# Easy_LED.net
KiCad netlist of a schematic drawn in EAGLE
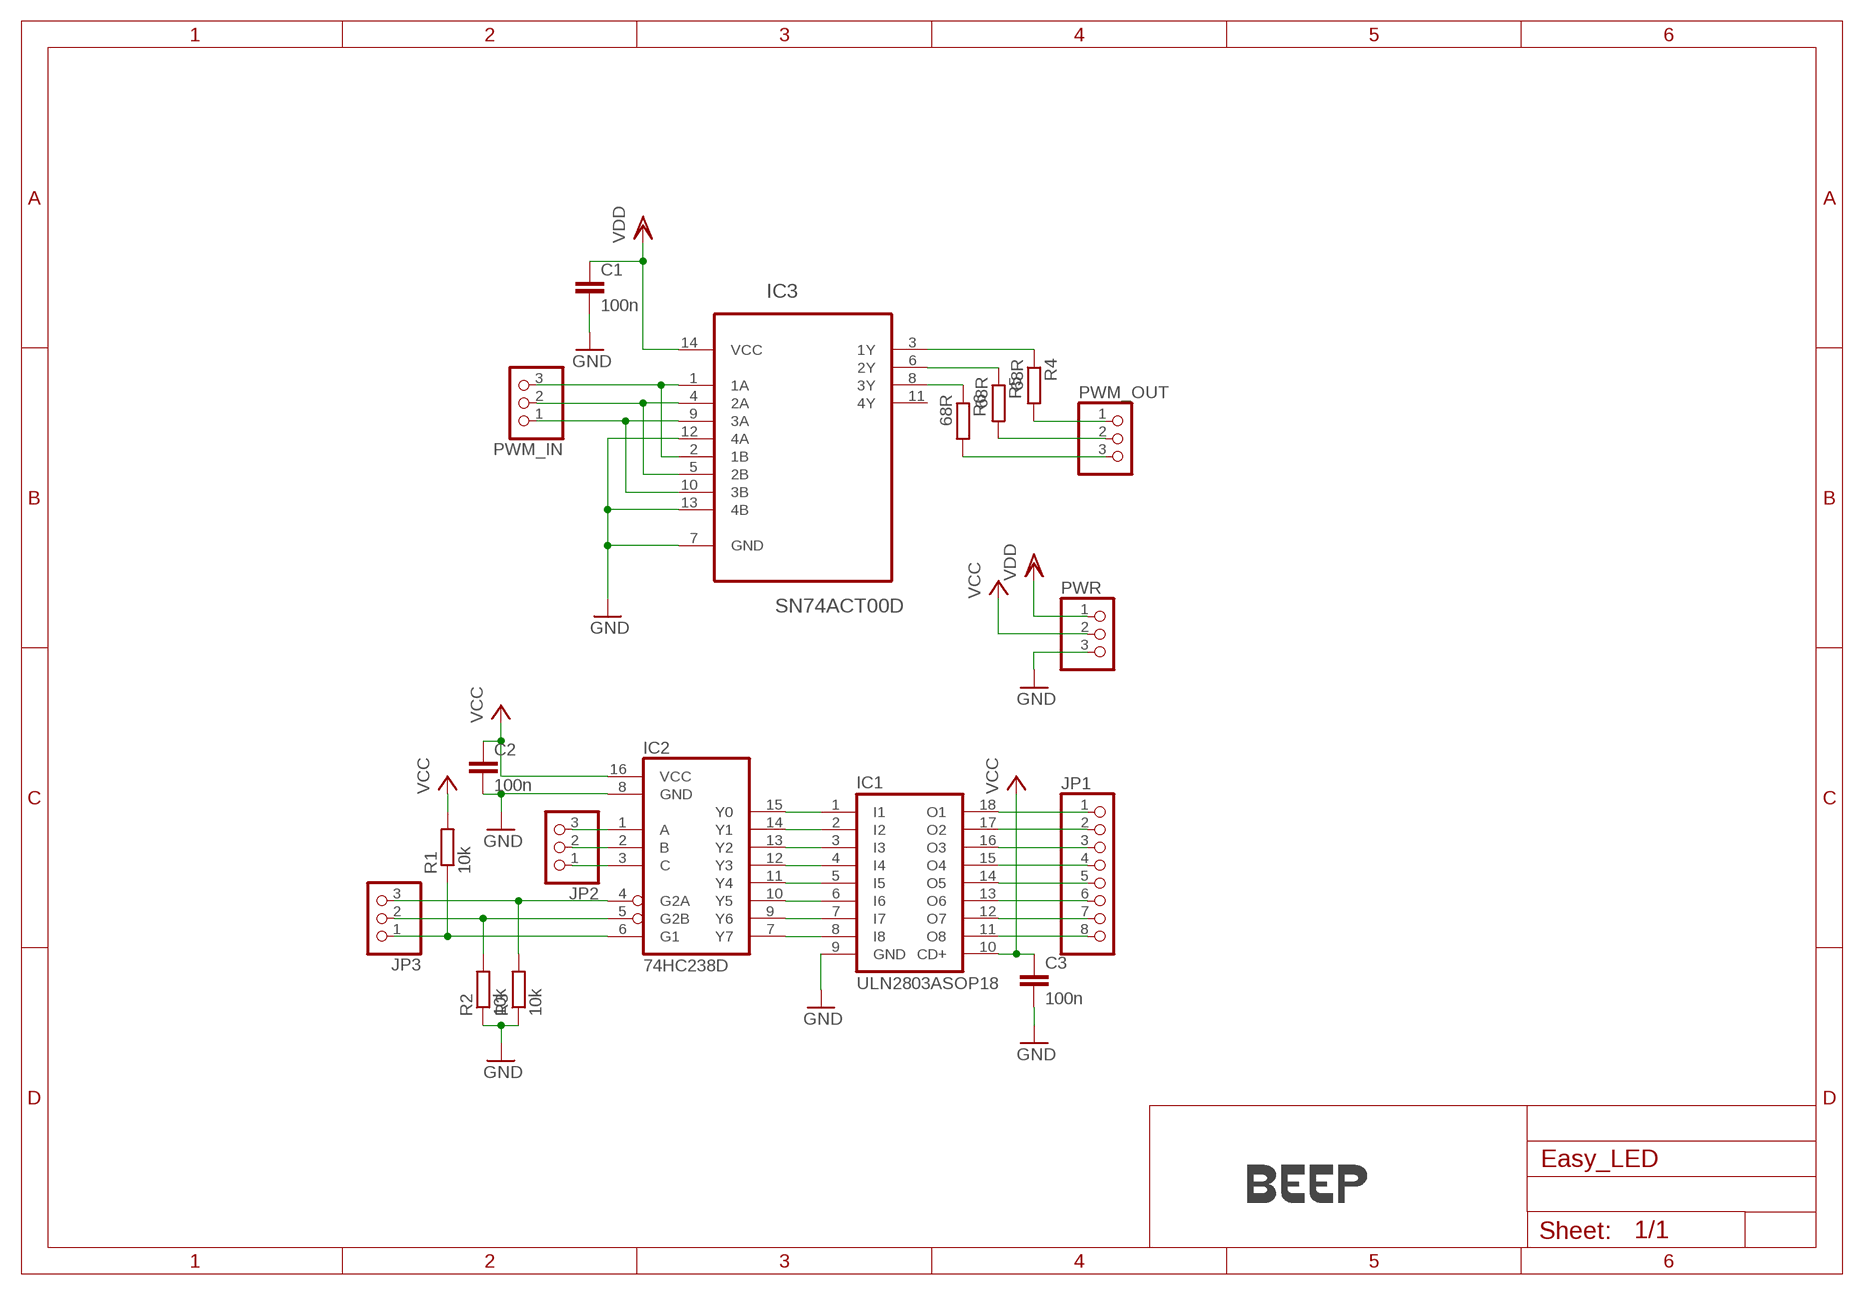
[diagram p0: schematic, sheet 1]

(export (version "E")
  (design (tool "Eeschema 10.0.6"))
  (components
    (comp (ref "C1")
      (value "100n")
      (footprint "eagle-import:C0805")
      (libsource (lib "eagle-import") (part "C-EUC0805"))
    )
    (comp (ref "C2")
      (value "100n")
      (footprint "eagle-import:C0805")
      (libsource (lib "eagle-import") (part "C-EUC0805"))
    )
    (comp (ref "C3")
      (value "100n")
      (footprint "eagle-import:C0805")
      (libsource (lib "eagle-import") (part "C-EUC0805"))
    )
    (comp (ref "IC1")
      (value "ULN2803ASOP18")
      (footprint "eagle-import:SOP18")
      (libsource (lib "eagle-import") (part "ULN2803ASOP18"))
    )
    (comp (ref "IC2")
      (value "74HC238D")
      (footprint "eagle-import:SO16")
      (libsource (lib "eagle-import") (part "74HC238D"))
    )
    (comp (ref "IC3")
      (value "SN74ACT00D")
      (footprint "eagle-import:SOIC127P600X175-14N")
      (libsource (lib "eagle-import") (part "SN74ACT00D"))
    )
    (comp (ref "JP1")
      (value "PINHD-1X8")
      (footprint "eagle-import:1X08")
      (libsource (lib "eagle-import") (part "PINHD-1X8"))
    )
    (comp (ref "JP2")
      (value "PINHD-1X3")
      (footprint "eagle-import:1X03")
      (libsource (lib "eagle-import") (part "PINHD-1X3"))
    )
    (comp (ref "JP3")
      (value "PINHD-1X3")
      (footprint "eagle-import:1X03")
      (libsource (lib "eagle-import") (part "PINHD-1X3"))
    )
    (comp (ref "PWM_IN")
      (value "PINHD-1X3")
      (footprint "eagle-import:1X03")
      (libsource (lib "eagle-import") (part "PINHD-1X3"))
    )
    (comp (ref "PWM_OUT")
      (value "PINHD-1X3")
      (footprint "eagle-import:1X03")
      (libsource (lib "eagle-import") (part "PINHD-1X3"))
    )
    (comp (ref "PWR")
      (value "PINHD-1X3")
      (footprint "eagle-import:1X03")
      (libsource (lib "eagle-import") (part "PINHD-1X3"))
    )
    (comp (ref "R1")
      (value "10k")
      (footprint "eagle-import:0207_7")
      (libsource (lib "eagle-import") (part "R-EU_0207/7"))
    )
    (comp (ref "R2")
      (value "10k")
      (footprint "eagle-import:M0805")
      (libsource (lib "eagle-import") (part "R-EU_M0805"))
    )
    (comp (ref "R3")
      (value "10k")
      (footprint "eagle-import:M0805")
      (libsource (lib "eagle-import") (part "R-EU_M0805"))
    )
    (comp (ref "R4")
      (value "68R")
      (footprint "eagle-import:M0805")
      (libsource (lib "eagle-import") (part "R-EU_M0805"))
    )
    (comp (ref "R5")
      (value "68R")
      (footprint "eagle-import:M0805")
      (libsource (lib "eagle-import") (part "R-EU_M0805"))
    )
    (comp (ref "R6")
      (value "68R")
      (footprint "eagle-import:M0805")
      (libsource (lib "eagle-import") (part "R-EU_M0805"))
    )
    (comp (ref "U$4")
      (value "LOGO-COPPER6")
      (footprint "eagle-import:COPPER6")
      (libsource (lib "eagle-import") (part "LOGO-COPPER6"))
    )
  )
  (nets
    (net (code "1") (name "GND") (class "Default")
      (node (ref "C1") (pin "2") (pinfunction "2_2") (pintype "passive"))
      (node (ref "C2") (pin "2") (pinfunction "2_2") (pintype "passive"))
      (node (ref "C3") (pin "2") (pinfunction "2_2") (pintype "passive"))
      (node (ref "IC1") (pin "9") (pinfunction "GND_9") (pintype "power_in"))
      (node (ref "IC2") (pin "8") (pinfunction "GND_8") (pintype "power_in"))
      (node (ref "IC3") (pin "12") (pinfunction "4A_12") (pintype "input"))
      (node (ref "IC3") (pin "13") (pinfunction "4B_13") (pintype "input"))
      (node (ref "IC3") (pin "7") (pinfunction "GND_7") (pintype "passive"))
      (node (ref "PWR") (pin "3") (pinfunction "3_3") (pintype "passive"))
      (node (ref "R2") (pin "1") (pinfunction "1_1") (pintype "passive"))
      (node (ref "R3") (pin "1") (pinfunction "1_1") (pintype "passive"))
    )
    (net (code "2") (name "Net-(IC1-I1)") (class "Default")
      (node (ref "IC1") (pin "1") (pinfunction "I1_1") (pintype "input"))
      (node (ref "IC2") (pin "15") (pinfunction "Y0_15") (pintype "output"))
    )
    (net (code "3") (name "Net-(IC1-I2)") (class "Default")
      (node (ref "IC1") (pin "2") (pinfunction "I2_2") (pintype "input"))
      (node (ref "IC2") (pin "14") (pinfunction "Y1_14") (pintype "output"))
    )
    (net (code "4") (name "Net-(IC1-I3)") (class "Default")
      (node (ref "IC1") (pin "3") (pinfunction "I3_3") (pintype "input"))
      (node (ref "IC2") (pin "13") (pinfunction "Y2_13") (pintype "output"))
    )
    (net (code "5") (name "Net-(IC1-I4)") (class "Default")
      (node (ref "IC1") (pin "4") (pinfunction "I4_4") (pintype "input"))
      (node (ref "IC2") (pin "12") (pinfunction "Y3_12") (pintype "output"))
    )
    (net (code "6") (name "Net-(IC1-I5)") (class "Default")
      (node (ref "IC1") (pin "5") (pinfunction "I5_5") (pintype "input"))
      (node (ref "IC2") (pin "11") (pinfunction "Y4_11") (pintype "output"))
    )
    (net (code "7") (name "Net-(IC1-I6)") (class "Default")
      (node (ref "IC1") (pin "6") (pinfunction "I6_6") (pintype "input"))
      (node (ref "IC2") (pin "10") (pinfunction "Y5_10") (pintype "output"))
    )
    (net (code "8") (name "Net-(IC1-I7)") (class "Default")
      (node (ref "IC1") (pin "7") (pinfunction "I7_7") (pintype "input"))
      (node (ref "IC2") (pin "9") (pinfunction "Y6_9") (pintype "output"))
    )
    (net (code "9") (name "Net-(IC1-I8)") (class "Default")
      (node (ref "IC1") (pin "8") (pinfunction "I8_8") (pintype "input"))
      (node (ref "IC2") (pin "7") (pinfunction "Y7_7") (pintype "output"))
    )
    (net (code "10") (name "Net-(IC1-O1)") (class "Default")
      (node (ref "IC1") (pin "18") (pinfunction "O1_18") (pintype "open_collector"))
      (node (ref "JP1") (pin "1") (pinfunction "1_1") (pintype "passive"))
    )
    (net (code "11") (name "Net-(IC1-O2)") (class "Default")
      (node (ref "IC1") (pin "17") (pinfunction "O2_17") (pintype "open_collector"))
      (node (ref "JP1") (pin "2") (pinfunction "2_2") (pintype "passive"))
    )
    (net (code "12") (name "Net-(IC1-O3)") (class "Default")
      (node (ref "IC1") (pin "16") (pinfunction "O3_16") (pintype "open_collector"))
      (node (ref "JP1") (pin "3") (pinfunction "3_3") (pintype "passive"))
    )
    (net (code "13") (name "Net-(IC1-O4)") (class "Default")
      (node (ref "IC1") (pin "15") (pinfunction "O4_15") (pintype "open_collector"))
      (node (ref "JP1") (pin "4") (pinfunction "4_4") (pintype "passive"))
    )
    (net (code "14") (name "Net-(IC1-O5)") (class "Default")
      (node (ref "IC1") (pin "14") (pinfunction "O5_14") (pintype "open_collector"))
      (node (ref "JP1") (pin "5") (pinfunction "5_5") (pintype "passive"))
    )
    (net (code "15") (name "Net-(IC1-O6)") (class "Default")
      (node (ref "IC1") (pin "13") (pinfunction "O6_13") (pintype "open_collector"))
      (node (ref "JP1") (pin "6") (pinfunction "6_6") (pintype "passive"))
    )
    (net (code "16") (name "Net-(IC1-O7)") (class "Default")
      (node (ref "IC1") (pin "12") (pinfunction "O7_12") (pintype "open_collector"))
      (node (ref "JP1") (pin "7") (pinfunction "7_7") (pintype "passive"))
    )
    (net (code "17") (name "Net-(IC1-O8)") (class "Default")
      (node (ref "IC1") (pin "11") (pinfunction "O8_11") (pintype "open_collector"))
      (node (ref "JP1") (pin "8") (pinfunction "8_8") (pintype "passive"))
    )
    (net (code "18") (name "Net-(IC2-A)") (class "Default")
      (node (ref "IC2") (pin "1") (pinfunction "A_1") (pintype "input"))
      (node (ref "JP2") (pin "3") (pinfunction "3_3") (pintype "passive"))
    )
    (net (code "19") (name "Net-(IC2-B)") (class "Default")
      (node (ref "IC2") (pin "2") (pinfunction "B_2") (pintype "input"))
      (node (ref "JP2") (pin "2") (pinfunction "2_2") (pintype "passive"))
    )
    (net (code "20") (name "Net-(IC2-C)") (class "Default")
      (node (ref "IC2") (pin "3") (pinfunction "C_3") (pintype "input"))
      (node (ref "JP2") (pin "1") (pinfunction "1_1") (pintype "passive"))
    )
    (net (code "21") (name "Net-(IC2-G1)") (class "Default")
      (node (ref "IC2") (pin "6") (pinfunction "G1_6") (pintype "input"))
      (node (ref "JP3") (pin "1") (pinfunction "1_1") (pintype "passive"))
      (node (ref "R1") (pin "1") (pinfunction "1_1") (pintype "passive"))
    )
    (net (code "22") (name "Net-(IC2-G2A)") (class "Default")
      (node (ref "IC2") (pin "4") (pinfunction "G2A_4") (pintype "input"))
      (node (ref "JP3") (pin "3") (pinfunction "3_3") (pintype "passive"))
      (node (ref "R3") (pin "2") (pinfunction "2_2") (pintype "passive"))
    )
    (net (code "23") (name "Net-(IC2-G2B)") (class "Default")
      (node (ref "IC2") (pin "5") (pinfunction "G2B_5") (pintype "input"))
      (node (ref "JP3") (pin "2") (pinfunction "2_2") (pintype "passive"))
      (node (ref "R2") (pin "2") (pinfunction "2_2") (pintype "passive"))
    )
    (net (code "24") (name "Net-(IC3-1A)") (class "Default")
      (node (ref "IC3") (pin "1") (pinfunction "1A_1") (pintype "input"))
      (node (ref "IC3") (pin "2") (pinfunction "1B_2") (pintype "input"))
      (node (ref "PWM_IN") (pin "3") (pinfunction "3_3") (pintype "passive"))
    )
    (net (code "25") (name "Net-(IC3-1Y)") (class "Default")
      (node (ref "IC3") (pin "3") (pinfunction "1Y_3") (pintype "output"))
      (node (ref "R4") (pin "1") (pinfunction "1_1") (pintype "passive"))
    )
    (net (code "26") (name "Net-(IC3-2A)") (class "Default")
      (node (ref "IC3") (pin "4") (pinfunction "2A_4") (pintype "input"))
      (node (ref "IC3") (pin "5") (pinfunction "2B_5") (pintype "input"))
      (node (ref "PWM_IN") (pin "2") (pinfunction "2_2") (pintype "passive"))
    )
    (net (code "27") (name "Net-(IC3-2Y)") (class "Default")
      (node (ref "IC3") (pin "6") (pinfunction "2Y_6") (pintype "output"))
      (node (ref "R5") (pin "1") (pinfunction "1_1") (pintype "passive"))
    )
    (net (code "28") (name "Net-(IC3-3A)") (class "Default")
      (node (ref "IC3") (pin "10") (pinfunction "3B_10") (pintype "input"))
      (node (ref "IC3") (pin "9") (pinfunction "3A_9") (pintype "input"))
      (node (ref "PWM_IN") (pin "1") (pinfunction "1_1") (pintype "passive"))
    )
    (net (code "29") (name "Net-(IC3-3Y)") (class "Default")
      (node (ref "IC3") (pin "8") (pinfunction "3Y_8") (pintype "output"))
      (node (ref "R6") (pin "1") (pinfunction "1_1") (pintype "passive"))
    )
    (net (code "30") (name "Net-(PWM_OUT-Pad1)") (class "Default")
      (node (ref "PWM_OUT") (pin "1") (pinfunction "1_1") (pintype "passive"))
      (node (ref "R4") (pin "2") (pinfunction "2_2") (pintype "passive"))
    )
    (net (code "31") (name "Net-(PWM_OUT-Pad2)") (class "Default")
      (node (ref "PWM_OUT") (pin "2") (pinfunction "2_2") (pintype "passive"))
      (node (ref "R5") (pin "2") (pinfunction "2_2") (pintype "passive"))
    )
    (net (code "32") (name "Net-(PWM_OUT-Pad3)") (class "Default")
      (node (ref "PWM_OUT") (pin "3") (pinfunction "3_3") (pintype "passive"))
      (node (ref "R6") (pin "2") (pinfunction "2_2") (pintype "passive"))
    )
    (net (code "33") (name "VCC") (class "Default")
      (node (ref "C2") (pin "1") (pinfunction "1_1") (pintype "passive"))
      (node (ref "C3") (pin "1") (pinfunction "1_1") (pintype "passive"))
      (node (ref "IC1") (pin "10") (pinfunction "CD+_10") (pintype "passive"))
      (node (ref "IC2") (pin "16") (pinfunction "VCC_16") (pintype "power_in"))
      (node (ref "PWR") (pin "2") (pinfunction "2_2") (pintype "passive"))
      (node (ref "R1") (pin "2") (pinfunction "2_2") (pintype "passive"))
    )
    (net (code "34") (name "VDD") (class "Default")
      (node (ref "C1") (pin "1") (pinfunction "1_1") (pintype "passive"))
      (node (ref "IC3") (pin "14") (pinfunction "VCC_14") (pintype "power_in"))
      (node (ref "PWR") (pin "1") (pinfunction "1_1") (pintype "passive"))
    )
    (net (code "35") (name "unconnected-(IC3-4Y-Pad11)") (class "Default")
      (node (ref "IC3") (pin "11") (pinfunction "4Y_11") (pintype "output"))
    )
  )
)
